# watch_main_final.net
KiCad netlist of a schematic drawn in EAGLE
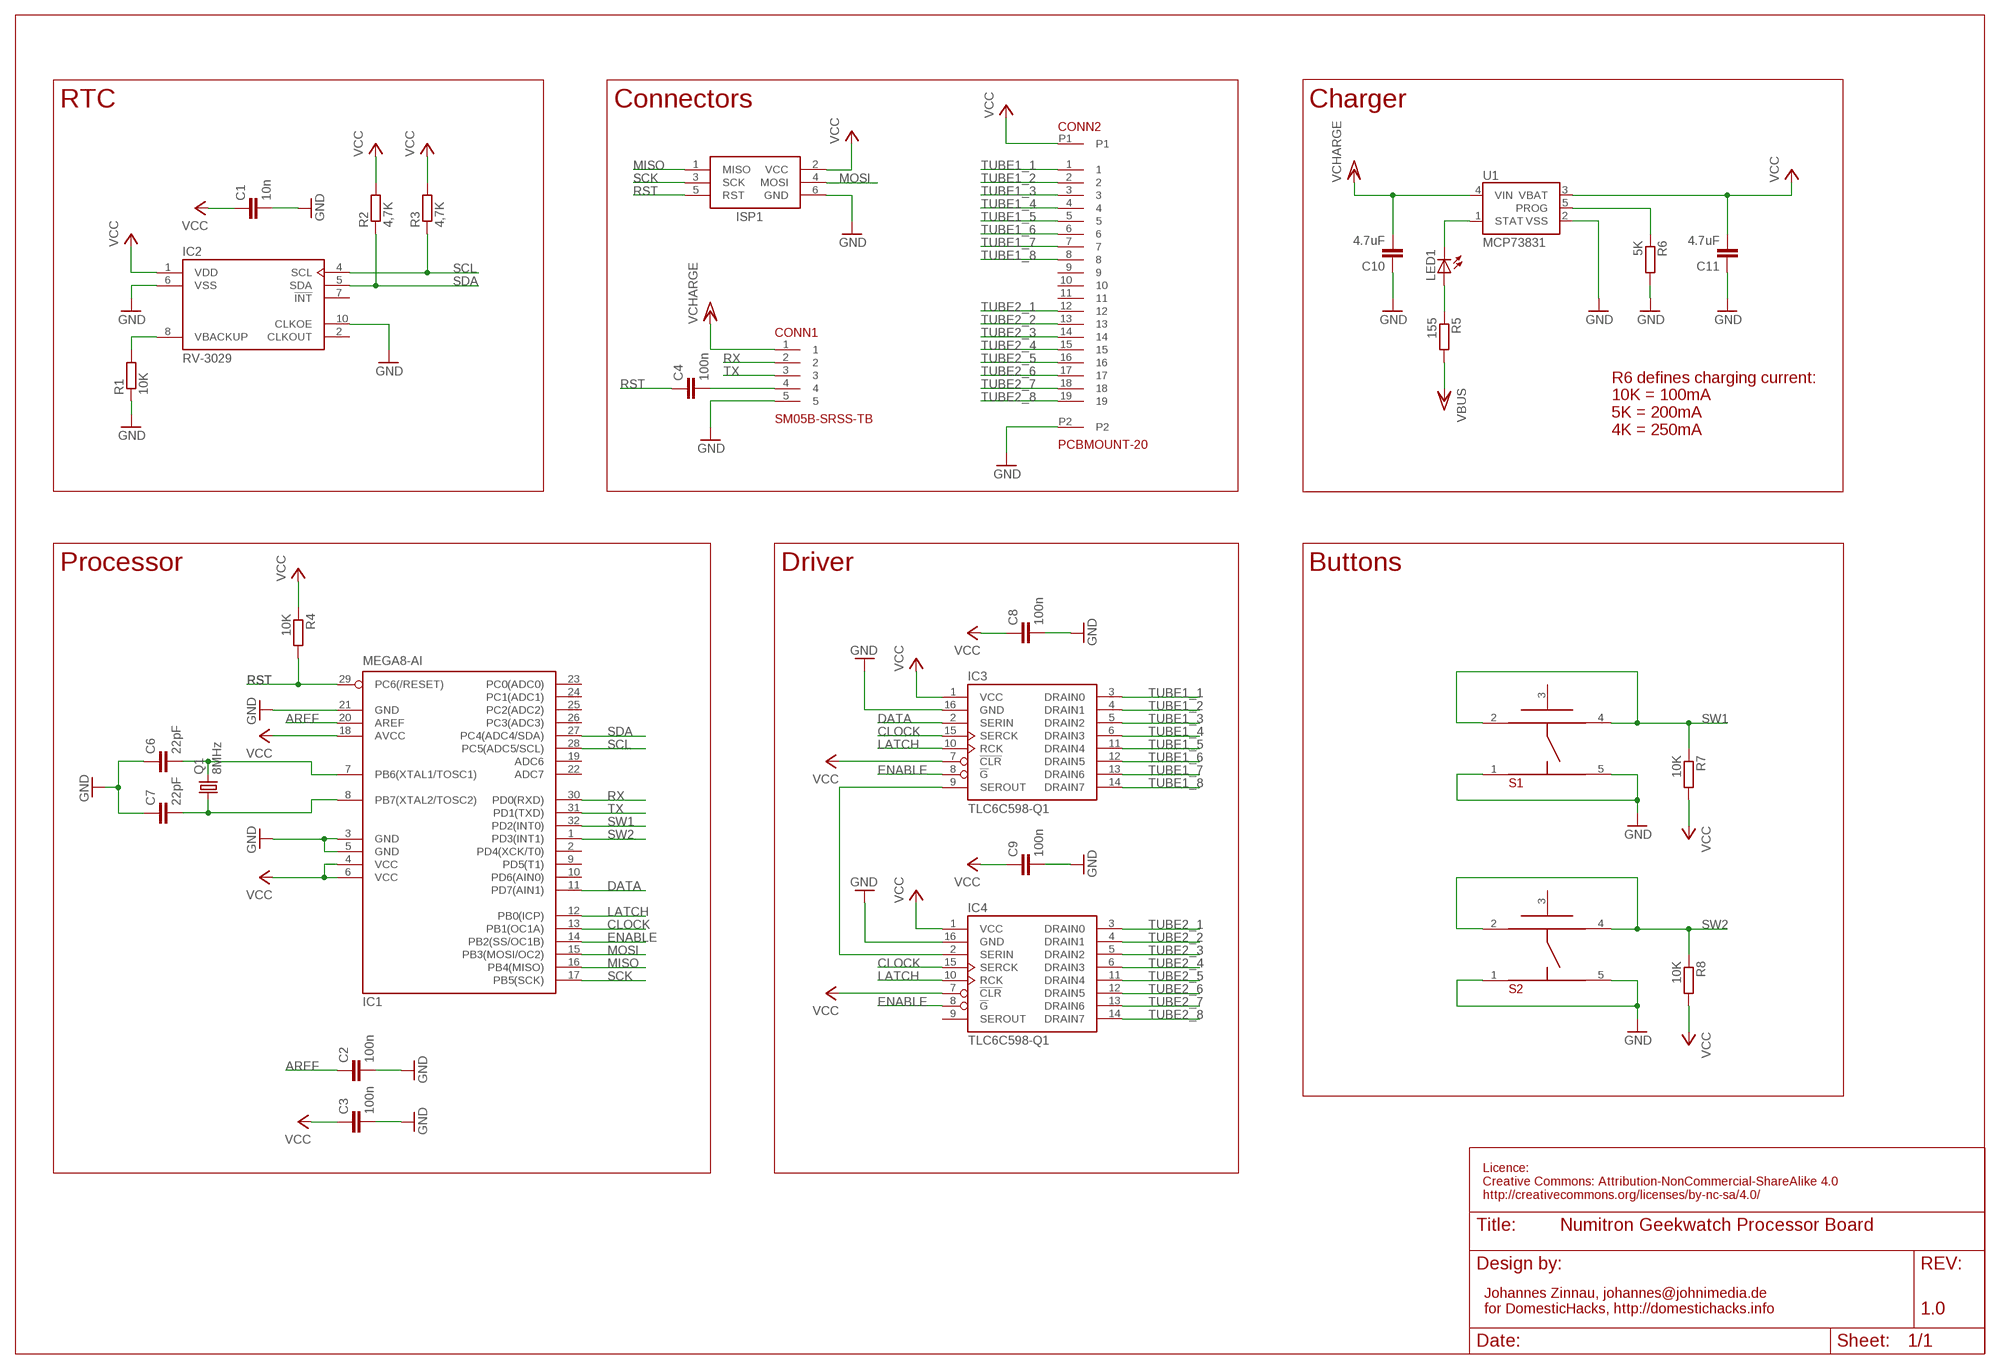
[diagram p0: schematic, sheet 1]

(export (version "E")
  (design (tool "Eeschema 10.0.6"))
  (components
    (comp (ref "C1")
      (value "10n")
      (footprint "eagle-import:C0603")
      (libsource (lib "eagle-import") (part "resistor_C-EUC0603"))
    )
    (comp (ref "C2")
      (value "100n")
      (footprint "eagle-import:C0603")
      (libsource (lib "eagle-import") (part "C-EUC0603"))
    )
    (comp (ref "C3")
      (value "100n")
      (footprint "eagle-import:C0603")
      (libsource (lib "eagle-import") (part "C-EUC0603"))
    )
    (comp (ref "C4")
      (value "100n")
      (footprint "eagle-import:C0603")
      (libsource (lib "eagle-import") (part "resistor_C-EUC0603"))
    )
    (comp (ref "C6")
      (value "22pF")
      (footprint "eagle-import:C0603")
      (libsource (lib "eagle-import") (part "C-EUC0603"))
    )
    (comp (ref "C7")
      (value "22pF")
      (footprint "eagle-import:C0603")
      (libsource (lib "eagle-import") (part "C-EUC0603"))
    )
    (comp (ref "C8")
      (value "100n")
      (footprint "eagle-import:C0603")
      (libsource (lib "eagle-import") (part "resistor_C-EUC0603"))
    )
    (comp (ref "C9")
      (value "100n")
      (footprint "eagle-import:C0603")
      (libsource (lib "eagle-import") (part "resistor_C-EUC0603"))
    )
    (comp (ref "C10")
      (value "4.7uF")
      (footprint "eagle-import:C0603")
      (libsource (lib "eagle-import") (part "resistor_C-EUC0603"))
    )
    (comp (ref "C11")
      (value "4.7uF")
      (footprint "eagle-import:C0603")
      (libsource (lib "eagle-import") (part "resistor_C-EUC0603"))
    )
    (comp (ref "CONN1")
      (value "SM05B-SRSS-TB")
      (footprint "eagle-import:JST-SR-SIDE-5")
      (libsource (lib "eagle-import") (part "SM05B-SRSS-TB"))
    )
    (comp (ref "CONN2")
      (value "PCBMOUNT-20")
      (footprint "eagle-import:PCBMOUNT-VERTICAL-20")
      (libsource (lib "eagle-import") (part "PCBMOUNT-20"))
    )
    (comp (ref "IC1")
      (value "MEGA8-AI")
      (footprint "eagle-import:TQFP32-08")
      (fields (field (name "MPN") "ATMEGA8-16AU"))
      (libsource (lib "eagle-import") (part "MEGA8-AI"))
    )
    (comp (ref "IC2")
      (value "RV-3029")
      (footprint "eagle-import:RV-3029-C2")
      (libsource (lib "eagle-import") (part "RV-3029"))
    )
    (comp (ref "IC3")
      (value "TLC6C598-Q1")
      (footprint "eagle-import:TSSOP-16")
      (libsource (lib "eagle-import") (part "TLC6C598-Q1"))
    )
    (comp (ref "IC4")
      (value "TLC6C598-Q1")
      (footprint "eagle-import:TSSOP-16")
      (libsource (lib "eagle-import") (part "TLC6C598-Q1"))
    )
    (comp (ref "ISP1")
      (value "AVRISP-6")
      (footprint "eagle-import:AVRISP")
      (libsource (lib "eagle-import") (part "AVRISP-6"))
    )
    (comp (ref "LED1")
      (value "HSMA/C/L-C120FLIPPED")
      (footprint "eagle-import:LED-0603-SIDE-FLIPPED")
      (libsource (lib "eagle-import") (part "HSMA/C/L-C120FLIPPED"))
    )
    (comp (ref "Q1")
      (value "8MHz")
      (footprint "eagle-import:MQ")
      (libsource (lib "eagle-import") (part "CRYSTALMQ"))
    )
    (comp (ref "R1")
      (value "10K")
      (footprint "eagle-import:R0603")
      (libsource (lib "eagle-import") (part "R-EU_R0603"))
    )
    (comp (ref "R2")
      (value "4,7K")
      (footprint "eagle-import:R0603")
      (libsource (lib "eagle-import") (part "R-EU_R0603"))
    )
    (comp (ref "R3")
      (value "4,7K")
      (footprint "eagle-import:R0603")
      (libsource (lib "eagle-import") (part "R-EU_R0603"))
    )
    (comp (ref "R4")
      (value "10K")
      (footprint "eagle-import:R0603")
      (libsource (lib "eagle-import") (part "R-EU_R0603"))
    )
    (comp (ref "R5")
      (value "155")
      (footprint "eagle-import:R0603")
      (libsource (lib "eagle-import") (part "R-EU_R0603"))
    )
    (comp (ref "R6")
      (value "5K")
      (footprint "eagle-import:R0603")
      (libsource (lib "eagle-import") (part "R-EU_R0603"))
    )
    (comp (ref "R7")
      (value "10K")
      (footprint "eagle-import:R0603")
      (libsource (lib "eagle-import") (part "R-EU_R0603"))
    )
    (comp (ref "R8")
      (value "10K")
      (footprint "eagle-import:R0603")
      (libsource (lib "eagle-import") (part "R-EU_R0603"))
    )
    (comp (ref "S1")
      (value "KMSXXXG")
      (footprint "eagle-import:C&K-KMS-SWITCH")
      (libsource (lib "eagle-import") (part "KMSXXXG"))
    )
    (comp (ref "S2")
      (value "KMSXXXG")
      (footprint "eagle-import:C&K-KMS-SWITCH")
      (libsource (lib "eagle-import") (part "KMSXXXG"))
    )
    (comp (ref "U1")
      (value "MCP73831")
      (footprint "eagle-import:SOT23-5")
      (libsource (lib "eagle-import") (part "MCP73831"))
    )
  )
  (nets
    (net (code "1") (name "/AREF") (class "Default")
      (node (ref "C2") (pin "1") (pinfunction "1_1") (pintype "passive"))
      (node (ref "IC1") (pin "20") (pinfunction "AREF_20") (pintype "passive"))
    )
    (net (code "2") (name "/CLOCK") (class "Default")
      (node (ref "IC1") (pin "13") (pinfunction "PB1(OC1A)_13") (pintype "bidirectional"))
      (node (ref "IC3") (pin "15") (pinfunction "SERCK_15") (pintype "input"))
      (node (ref "IC4") (pin "15") (pinfunction "SERCK_15") (pintype "input"))
    )
    (net (code "3") (name "/DATA") (class "Default")
      (node (ref "IC1") (pin "11") (pinfunction "PD7(AIN1)_11") (pintype "bidirectional"))
      (node (ref "IC3") (pin "2") (pinfunction "SERIN_2") (pintype "input"))
    )
    (net (code "4") (name "/ENABLE") (class "Default")
      (node (ref "IC1") (pin "14") (pinfunction "PB2(SS/OC1B)_14") (pintype "bidirectional"))
      (node (ref "IC3") (pin "8") (pinfunction "~{G}_8") (pintype "input"))
      (node (ref "IC4") (pin "8") (pinfunction "~{G}_8") (pintype "input"))
    )
    (net (code "5") (name "/LATCH") (class "Default")
      (node (ref "IC1") (pin "12") (pinfunction "PB0(ICP)_12") (pintype "bidirectional"))
      (node (ref "IC3") (pin "10") (pinfunction "RCK_10") (pintype "input"))
      (node (ref "IC4") (pin "10") (pinfunction "RCK_10") (pintype "input"))
    )
    (net (code "6") (name "/MISO") (class "Default")
      (node (ref "IC1") (pin "16") (pinfunction "PB4(MISO)_16") (pintype "bidirectional"))
      (node (ref "ISP1") (pin "1") (pinfunction "MISO_1") (pintype "input"))
    )
    (net (code "7") (name "/MOSI") (class "Default")
      (node (ref "IC1") (pin "15") (pinfunction "PB3(MOSI/OC2)_15") (pintype "bidirectional"))
      (node (ref "ISP1") (pin "4") (pinfunction "MOSI_4") (pintype "output"))
    )
    (net (code "8") (name "/RST") (class "Default")
      (node (ref "C4") (pin "1") (pinfunction "1_1") (pintype "passive"))
      (node (ref "IC1") (pin "29") (pinfunction "PC6(/RESET)_29") (pintype "bidirectional"))
      (node (ref "ISP1") (pin "5") (pinfunction "RST_5") (pintype "output"))
      (node (ref "R4") (pin "2") (pinfunction "2_2") (pintype "passive"))
    )
    (net (code "9") (name "/RX") (class "Default")
      (node (ref "CONN1") (pin "2") (pinfunction "2_2") (pintype "bidirectional"))
      (node (ref "IC1") (pin "30") (pinfunction "PD0(RXD)_30") (pintype "bidirectional"))
    )
    (net (code "10") (name "/SCK") (class "Default")
      (node (ref "IC1") (pin "17") (pinfunction "PB5(SCK)_17") (pintype "bidirectional"))
      (node (ref "ISP1") (pin "3") (pinfunction "SCK_3") (pintype "output"))
    )
    (net (code "11") (name "/SCL") (class "Default")
      (node (ref "IC1") (pin "28") (pinfunction "PC5(ADC5/SCL)_28") (pintype "bidirectional"))
      (node (ref "IC2") (pin "4") (pinfunction "SCL_4") (pintype "input"))
      (node (ref "R3") (pin "1") (pinfunction "1_1") (pintype "passive"))
    )
    (net (code "12") (name "/SDA") (class "Default")
      (node (ref "IC1") (pin "27") (pinfunction "PC4(ADC4/SDA)_27") (pintype "bidirectional"))
      (node (ref "IC2") (pin "5") (pinfunction "SDA_5") (pintype "bidirectional"))
      (node (ref "R2") (pin "1") (pinfunction "1_1") (pintype "passive"))
    )
    (net (code "13") (name "/SW1") (class "Default")
      (node (ref "IC1") (pin "32") (pinfunction "PD2(INT0)_32") (pintype "bidirectional"))
      (node (ref "R7") (pin "1") (pinfunction "1_1") (pintype "passive"))
      (node (ref "S1") (pin "2") (pinfunction "2_2") (pintype "bidirectional"))
      (node (ref "S1") (pin "4") (pinfunction "4_4") (pintype "bidirectional"))
    )
    (net (code "14") (name "/SW2") (class "Default")
      (node (ref "IC1") (pin "1") (pinfunction "PD3(INT1)_1") (pintype "bidirectional"))
      (node (ref "R8") (pin "1") (pinfunction "1_1") (pintype "passive"))
      (node (ref "S2") (pin "2") (pinfunction "2_2") (pintype "bidirectional"))
      (node (ref "S2") (pin "4") (pinfunction "4_4") (pintype "bidirectional"))
    )
    (net (code "15") (name "/TUBE1_1") (class "Default")
      (node (ref "CONN2") (pin "1") (pinfunction "1_1") (pintype "bidirectional"))
      (node (ref "IC3") (pin "3") (pinfunction "DRAIN0_3") (pintype "output"))
    )
    (net (code "16") (name "/TUBE1_2") (class "Default")
      (node (ref "CONN2") (pin "2") (pinfunction "2_2") (pintype "bidirectional"))
      (node (ref "IC3") (pin "4") (pinfunction "DRAIN1_4") (pintype "output"))
    )
    (net (code "17") (name "/TUBE1_3") (class "Default")
      (node (ref "CONN2") (pin "3") (pinfunction "3_3") (pintype "bidirectional"))
      (node (ref "IC3") (pin "5") (pinfunction "DRAIN2_5") (pintype "output"))
    )
    (net (code "18") (name "/TUBE1_4") (class "Default")
      (node (ref "CONN2") (pin "4") (pinfunction "4_4") (pintype "bidirectional"))
      (node (ref "IC3") (pin "6") (pinfunction "DRAIN3_6") (pintype "output"))
    )
    (net (code "19") (name "/TUBE1_5") (class "Default")
      (node (ref "CONN2") (pin "5") (pinfunction "5_5") (pintype "bidirectional"))
      (node (ref "IC3") (pin "11") (pinfunction "DRAIN4_11") (pintype "output"))
    )
    (net (code "20") (name "/TUBE1_6") (class "Default")
      (node (ref "CONN2") (pin "6") (pinfunction "6_6") (pintype "bidirectional"))
      (node (ref "IC3") (pin "12") (pinfunction "DRAIN5_12") (pintype "output"))
    )
    (net (code "21") (name "/TUBE1_7") (class "Default")
      (node (ref "CONN2") (pin "7") (pinfunction "7_7") (pintype "bidirectional"))
      (node (ref "IC3") (pin "13") (pinfunction "DRAIN6_13") (pintype "output"))
    )
    (net (code "22") (name "/TUBE1_8") (class "Default")
      (node (ref "CONN2") (pin "8") (pinfunction "8_8") (pintype "bidirectional"))
      (node (ref "IC3") (pin "14") (pinfunction "DRAIN7_14") (pintype "output"))
    )
    (net (code "23") (name "/TUBE2_1") (class "Default")
      (node (ref "CONN2") (pin "12") (pinfunction "12_12") (pintype "bidirectional"))
      (node (ref "IC4") (pin "3") (pinfunction "DRAIN0_3") (pintype "output"))
    )
    (net (code "24") (name "/TUBE2_2") (class "Default")
      (node (ref "CONN2") (pin "13") (pinfunction "13_13") (pintype "bidirectional"))
      (node (ref "IC4") (pin "4") (pinfunction "DRAIN1_4") (pintype "output"))
    )
    (net (code "25") (name "/TUBE2_3") (class "Default")
      (node (ref "CONN2") (pin "14") (pinfunction "14_14") (pintype "bidirectional"))
      (node (ref "IC4") (pin "5") (pinfunction "DRAIN2_5") (pintype "output"))
    )
    (net (code "26") (name "/TUBE2_4") (class "Default")
      (node (ref "CONN2") (pin "15") (pinfunction "15_15") (pintype "bidirectional"))
      (node (ref "IC4") (pin "6") (pinfunction "DRAIN3_6") (pintype "output"))
    )
    (net (code "27") (name "/TUBE2_5") (class "Default")
      (node (ref "CONN2") (pin "16") (pinfunction "16_16") (pintype "bidirectional"))
      (node (ref "IC4") (pin "11") (pinfunction "DRAIN4_11") (pintype "output"))
    )
    (net (code "28") (name "/TUBE2_6") (class "Default")
      (node (ref "CONN2") (pin "17") (pinfunction "17_17") (pintype "bidirectional"))
      (node (ref "IC4") (pin "12") (pinfunction "DRAIN5_12") (pintype "output"))
    )
    (net (code "29") (name "/TUBE2_7") (class "Default")
      (node (ref "CONN2") (pin "18") (pinfunction "18_18") (pintype "bidirectional"))
      (node (ref "IC4") (pin "13") (pinfunction "DRAIN6_13") (pintype "output"))
    )
    (net (code "30") (name "/TUBE2_8") (class "Default")
      (node (ref "CONN2") (pin "19") (pinfunction "19_19") (pintype "bidirectional"))
      (node (ref "IC4") (pin "14") (pinfunction "DRAIN7_14") (pintype "output"))
    )
    (net (code "31") (name "/TX") (class "Default")
      (node (ref "CONN1") (pin "3") (pinfunction "3_3") (pintype "bidirectional"))
      (node (ref "IC1") (pin "31") (pinfunction "PD1(TXD)_31") (pintype "bidirectional"))
    )
    (net (code "32") (name "GND") (class "Default")
      (node (ref "C1") (pin "2") (pinfunction "2_2") (pintype "passive"))
      (node (ref "C10") (pin "1") (pinfunction "1_1") (pintype "passive"))
      (node (ref "C11") (pin "1") (pinfunction "1_1") (pintype "passive"))
      (node (ref "C2") (pin "2") (pinfunction "2_2") (pintype "passive"))
      (node (ref "C3") (pin "2") (pinfunction "2_2") (pintype "passive"))
      (node (ref "C6") (pin "1") (pinfunction "1_1") (pintype "passive"))
      (node (ref "C7") (pin "1") (pinfunction "1_1") (pintype "passive"))
      (node (ref "C8") (pin "2") (pinfunction "2_2") (pintype "passive"))
      (node (ref "C9") (pin "2") (pinfunction "2_2") (pintype "passive"))
      (node (ref "CONN1") (pin "5") (pinfunction "5_5") (pintype "bidirectional"))
      (node (ref "CONN2") (pin "P2") (pinfunction "P2_P2") (pintype "bidirectional"))
      (node (ref "IC1") (pin "21") (pinfunction "GND_21") (pintype "power_in"))
      (node (ref "IC1") (pin "3") (pinfunction "GND_3") (pintype "power_in"))
      (node (ref "IC1") (pin "5") (pinfunction "GND_5") (pintype "power_in"))
      (node (ref "IC2") (pin "10") (pinfunction "CLKOE_10") (pintype "input"))
      (node (ref "IC2") (pin "6") (pinfunction "VSS_6") (pintype "input"))
      (node (ref "IC3") (pin "16") (pinfunction "GND_16") (pintype "input"))
      (node (ref "IC4") (pin "16") (pinfunction "GND_16") (pintype "input"))
      (node (ref "ISP1") (pin "6") (pinfunction "GND_6") (pintype "power_in"))
      (node (ref "R1") (pin "1") (pinfunction "1_1") (pintype "passive"))
      (node (ref "R6") (pin "2") (pinfunction "2_2") (pintype "passive"))
      (node (ref "S1") (pin "1") (pinfunction "1_1") (pintype "bidirectional"))
      (node (ref "S1") (pin "5") (pinfunction "5_5") (pintype "bidirectional"))
      (node (ref "S2") (pin "1") (pinfunction "1_1") (pintype "bidirectional"))
      (node (ref "S2") (pin "5") (pinfunction "5_5") (pintype "bidirectional"))
      (node (ref "U1") (pin "2") (pinfunction "VSS_2") (pintype "power_in"))
    )
    (net (code "33") (name "Net-(C4-Pad2)") (class "Default")
      (node (ref "C4") (pin "2") (pinfunction "2_2") (pintype "passive"))
      (node (ref "CONN1") (pin "4") (pinfunction "4_4") (pintype "bidirectional"))
    )
    (net (code "34") (name "Net-(IC1-PB6(XTAL1{slash}TOSC1))") (class "Default")
      (node (ref "C6") (pin "2") (pinfunction "2_2") (pintype "passive"))
      (node (ref "IC1") (pin "7") (pinfunction "PB6(XTAL1/TOSC1)_7") (pintype "bidirectional"))
      (node (ref "Q1") (pin "P3") (pinfunction "2_P3") (pintype "passive"))
    )
    (net (code "35") (name "Net-(IC1-PB7(XTAL2{slash}TOSC2))") (class "Default")
      (node (ref "C7") (pin "2") (pinfunction "2_2") (pintype "passive"))
      (node (ref "IC1") (pin "8") (pinfunction "PB7(XTAL2/TOSC2)_8") (pintype "bidirectional"))
      (node (ref "Q1") (pin "P1") (pinfunction "1_P1") (pintype "passive"))
    )
    (net (code "36") (name "Net-(IC2-VBACKUP)") (class "Default")
      (node (ref "IC2") (pin "8") (pinfunction "VBACKUP_8") (pintype "input"))
      (node (ref "R1") (pin "2") (pinfunction "2_2") (pintype "passive"))
    )
    (net (code "37") (name "Net-(IC3-SEROUT)") (class "Default")
      (node (ref "IC3") (pin "9") (pinfunction "SEROUT_9") (pintype "output"))
      (node (ref "IC4") (pin "2") (pinfunction "SERIN_2") (pintype "input"))
    )
    (net (code "38") (name "Net-(LED1-PadA)") (class "Default")
      (node (ref "LED1") (pin "A") (pinfunction "A_A") (pintype "passive"))
      (node (ref "R5") (pin "1") (pinfunction "1_1") (pintype "passive"))
    )
    (net (code "39") (name "Net-(U1-PROG)") (class "Default")
      (node (ref "R6") (pin "1") (pinfunction "1_1") (pintype "passive"))
      (node (ref "U1") (pin "5") (pinfunction "PROG_5") (pintype "input"))
    )
    (net (code "40") (name "Net-(U1-STAT)") (class "Default")
      (node (ref "LED1") (pin "C") (pinfunction "C_C") (pintype "passive"))
      (node (ref "U1") (pin "1") (pinfunction "STAT_1") (pintype "output"))
    )
    (net (code "41") (name "VBUS") (class "Default")
      (node (ref "C10") (pin "2") (pinfunction "2_2") (pintype "passive"))
      (node (ref "CONN1") (pin "1") (pinfunction "1_1") (pintype "bidirectional"))
      (node (ref "R5") (pin "2") (pinfunction "2_2") (pintype "passive"))
      (node (ref "U1") (pin "4") (pinfunction "VIN_4") (pintype "power_in"))
    )
    (net (code "42") (name "VCC") (class "Default")
      (node (ref "C1") (pin "1") (pinfunction "1_1") (pintype "passive"))
      (node (ref "C11") (pin "2") (pinfunction "2_2") (pintype "passive"))
      (node (ref "C3") (pin "1") (pinfunction "1_1") (pintype "passive"))
      (node (ref "C8") (pin "1") (pinfunction "1_1") (pintype "passive"))
      (node (ref "C9") (pin "1") (pinfunction "1_1") (pintype "passive"))
      (node (ref "CONN2") (pin "P1") (pinfunction "P1_P1") (pintype "bidirectional"))
      (node (ref "IC1") (pin "18") (pinfunction "AVCC_18") (pintype "power_in"))
      (node (ref "IC1") (pin "4") (pinfunction "VCC_4") (pintype "power_in"))
      (node (ref "IC1") (pin "6") (pinfunction "VCC_6") (pintype "power_in"))
      (node (ref "IC2") (pin "1") (pinfunction "VDD_1") (pintype "input"))
      (node (ref "IC3") (pin "1") (pinfunction "VCC_1") (pintype "input"))
      (node (ref "IC3") (pin "7") (pinfunction "~{CLR}_7") (pintype "input"))
      (node (ref "IC4") (pin "1") (pinfunction "VCC_1") (pintype "input"))
      (node (ref "IC4") (pin "7") (pinfunction "~{CLR}_7") (pintype "input"))
      (node (ref "ISP1") (pin "2") (pinfunction "VCC_2") (pintype "power_in"))
      (node (ref "R2") (pin "2") (pinfunction "2_2") (pintype "passive"))
      (node (ref "R3") (pin "2") (pinfunction "2_2") (pintype "passive"))
      (node (ref "R4") (pin "1") (pinfunction "1_1") (pintype "passive"))
      (node (ref "R7") (pin "2") (pinfunction "2_2") (pintype "passive"))
      (node (ref "R8") (pin "2") (pinfunction "2_2") (pintype "passive"))
      (node (ref "U1") (pin "3") (pinfunction "VBAT_3") (pintype "power_in"))
    )
    (net (code "43") (name "unconnected-(CONN2-Pad9)") (class "Default")
      (node (ref "CONN2") (pin "9") (pinfunction "9_9") (pintype "bidirectional"))
    )
    (net (code "44") (name "unconnected-(CONN2-Pad10)") (class "Default")
      (node (ref "CONN2") (pin "10") (pinfunction "10_10") (pintype "bidirectional"))
    )
    (net (code "45") (name "unconnected-(CONN2-Pad11)") (class "Default")
      (node (ref "CONN2") (pin "11") (pinfunction "11_11") (pintype "bidirectional"))
    )
    (net (code "46") (name "unconnected-(IC1-ADC6-Pad19)") (class "Default")
      (node (ref "IC1") (pin "19") (pinfunction "ADC6_19") (pintype "bidirectional"))
    )
    (net (code "47") (name "unconnected-(IC1-ADC7-Pad22)") (class "Default")
      (node (ref "IC1") (pin "22") (pinfunction "ADC7_22") (pintype "bidirectional"))
    )
    (net (code "48") (name "unconnected-(IC1-PC0(ADC0)-Pad23)") (class "Default")
      (node (ref "IC1") (pin "23") (pinfunction "PC0(ADC0)_23") (pintype "bidirectional"))
    )
    (net (code "49") (name "unconnected-(IC1-PC1(ADC1)-Pad24)") (class "Default")
      (node (ref "IC1") (pin "24") (pinfunction "PC1(ADC1)_24") (pintype "bidirectional"))
    )
    (net (code "50") (name "unconnected-(IC1-PC2(ADC2)-Pad25)") (class "Default")
      (node (ref "IC1") (pin "25") (pinfunction "PC2(ADC2)_25") (pintype "bidirectional"))
    )
    (net (code "51") (name "unconnected-(IC1-PC3(ADC3)-Pad26)") (class "Default")
      (node (ref "IC1") (pin "26") (pinfunction "PC3(ADC3)_26") (pintype "bidirectional"))
    )
    (net (code "52") (name "unconnected-(IC1-PD4(XCK{slash}T0)-Pad2)") (class "Default")
      (node (ref "IC1") (pin "2") (pinfunction "PD4(XCK/T0)_2") (pintype "bidirectional"))
    )
    (net (code "53") (name "unconnected-(IC1-PD5(T1)-Pad9)") (class "Default")
      (node (ref "IC1") (pin "9") (pinfunction "PD5(T1)_9") (pintype "bidirectional"))
    )
    (net (code "54") (name "unconnected-(IC1-PD6(AIN0)-Pad10)") (class "Default")
      (node (ref "IC1") (pin "10") (pinfunction "PD6(AIN0)_10") (pintype "bidirectional"))
    )
    (net (code "55") (name "unconnected-(IC2-CLKOUT-Pad2)") (class "Default")
      (node (ref "IC2") (pin "2") (pinfunction "CLKOUT_2") (pintype "output"))
    )
    (net (code "56") (name "unconnected-(IC2-~{INT}-Pad7)") (class "Default")
      (node (ref "IC2") (pin "7") (pinfunction "~{INT}_7") (pintype "output"))
    )
    (net (code "57") (name "unconnected-(IC4-SEROUT-Pad9)") (class "Default")
      (node (ref "IC4") (pin "9") (pinfunction "SEROUT_9") (pintype "output"))
    )
    (net (code "58") (name "unconnected-(S1-Pad3)") (class "Default")
      (node (ref "S1") (pin "3") (pinfunction "3_3") (pintype "bidirectional"))
    )
    (net (code "59") (name "unconnected-(S2-Pad3)") (class "Default")
      (node (ref "S2") (pin "3") (pinfunction "3_3") (pintype "bidirectional"))
    )
  )
)
